# FiltroRF.net
KiCad netlist of a schematic drawn in Altium Designer
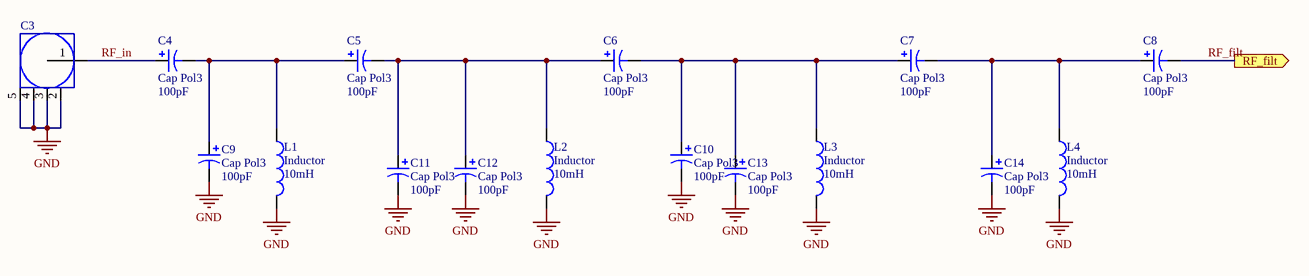
[diagram p0: FiltroRF.SchDoc]

(export (version "E")
  (design (tool "Eeschema 10.0.6"))
  (components
    (comp (ref "C3") (value "SMA") (footprint "SMA1") (libsource (lib "epf") (part "SMA")))
    (comp (ref "C4")
      (value "Cap Pol3")
      (footprint "C0805")
      (description "Polarized Capacitor (Surface Mount)")
      (fields (field (name "ALTIUM_VALUE") "100pF") (field (name "PUBLISHER") "Altium Limited"))
      (libsource (lib "Miscellaneous Devices") (part "Cap Pol3"))
    )
    (comp (ref "C5")
      (value "Cap Pol3")
      (footprint "C0805")
      (description "Polarized Capacitor (Surface Mount)")
      (fields (field (name "ALTIUM_VALUE") "100pF") (field (name "PUBLISHER") "Altium Limited"))
      (libsource (lib "Miscellaneous Devices") (part "Cap Pol3"))
    )
    (comp (ref "C6")
      (value "Cap Pol3")
      (footprint "C0805")
      (description "Polarized Capacitor (Surface Mount)")
      (fields (field (name "ALTIUM_VALUE") "100pF") (field (name "PUBLISHER") "Altium Limited"))
      (libsource (lib "Miscellaneous Devices") (part "Cap Pol3"))
    )
    (comp (ref "C7")
      (value "Cap Pol3")
      (footprint "C0805")
      (description "Polarized Capacitor (Surface Mount)")
      (fields (field (name "ALTIUM_VALUE") "100pF") (field (name "PUBLISHER") "Altium Limited"))
      (libsource (lib "Miscellaneous Devices") (part "Cap Pol3"))
    )
    (comp (ref "C8")
      (value "Cap Pol3")
      (footprint "C0805")
      (description "Polarized Capacitor (Surface Mount)")
      (fields (field (name "ALTIUM_VALUE") "100pF") (field (name "PUBLISHER") "Altium Limited"))
      (libsource (lib "Miscellaneous Devices") (part "Cap Pol3"))
    )
    (comp (ref "C9")
      (value "Cap Pol3")
      (footprint "C0805")
      (description "Polarized Capacitor (Surface Mount)")
      (fields (field (name "ALTIUM_VALUE") "100pF") (field (name "PUBLISHER") "Altium Limited"))
      (libsource (lib "Miscellaneous Devices") (part "Cap Pol3"))
    )
    (comp (ref "C10")
      (value "Cap Pol3")
      (footprint "C0805")
      (description "Polarized Capacitor (Surface Mount)")
      (fields (field (name "ALTIUM_VALUE") "100pF") (field (name "PUBLISHER") "Altium Limited"))
      (libsource (lib "Miscellaneous Devices") (part "Cap Pol3"))
    )
    (comp (ref "C11")
      (value "Cap Pol3")
      (footprint "C0805")
      (description "Polarized Capacitor (Surface Mount)")
      (fields (field (name "ALTIUM_VALUE") "100pF") (field (name "PUBLISHER") "Altium Limited"))
      (libsource (lib "Miscellaneous Devices") (part "Cap Pol3"))
    )
    (comp (ref "C12")
      (value "Cap Pol3")
      (footprint "C0805")
      (description "Polarized Capacitor (Surface Mount)")
      (fields (field (name "ALTIUM_VALUE") "100pF") (field (name "PUBLISHER") "Altium Limited"))
      (libsource (lib "Miscellaneous Devices") (part "Cap Pol3"))
    )
    (comp (ref "C13")
      (value "Cap Pol3")
      (footprint "C0805")
      (description "Polarized Capacitor (Surface Mount)")
      (fields (field (name "ALTIUM_VALUE") "100pF") (field (name "PUBLISHER") "Altium Limited"))
      (libsource (lib "Miscellaneous Devices") (part "Cap Pol3"))
    )
    (comp (ref "C14")
      (value "Cap Pol3")
      (footprint "C0805")
      (description "Polarized Capacitor (Surface Mount)")
      (fields (field (name "ALTIUM_VALUE") "100pF") (field (name "PUBLISHER") "Altium Limited"))
      (libsource (lib "Miscellaneous Devices") (part "Cap Pol3"))
    )
    (comp (ref "L1")
      (value "Inductor")
      (footprint "3261")
      (fields (field (name "ALTIUM_VALUE") "10mH") (field (name "PUBLISHER") "Altium Limited"))
      (libsource (lib "Miscellaneous Devices") (part "Inductor"))
    )
    (comp (ref "L2")
      (value "Inductor")
      (footprint "3261")
      (fields (field (name "ALTIUM_VALUE") "10mH") (field (name "PUBLISHER") "Altium Limited"))
      (libsource (lib "Miscellaneous Devices") (part "Inductor"))
    )
    (comp (ref "L3")
      (value "Inductor")
      (footprint "3261")
      (fields (field (name "ALTIUM_VALUE") "10mH") (field (name "PUBLISHER") "Altium Limited"))
      (libsource (lib "Miscellaneous Devices") (part "Inductor"))
    )
    (comp (ref "L4")
      (value "Inductor")
      (footprint "3261")
      (fields (field (name "ALTIUM_VALUE") "10mH") (field (name "PUBLISHER") "Altium Limited"))
      (libsource (lib "Miscellaneous Devices") (part "Inductor"))
    )
  )
  (nets
    (net (code "1") (name "/RF_filt") (class "Default")
      (node (ref "C8") (pin "2") (pinfunction "2_2") (pintype "passive"))
    )
    (net (code "2") (name "/RF_in") (class "Default")
      (node (ref "C3") (pin "1") (pinfunction "RF_1") (pintype "passive"))
      (node (ref "C4") (pin "1") (pinfunction "1_1") (pintype "passive"))
    )
    (net (code "3") (name "GND") (class "Default")
      (node (ref "C10") (pin "2") (pinfunction "2_2") (pintype "passive"))
      (node (ref "C11") (pin "2") (pinfunction "2_2") (pintype "passive"))
      (node (ref "C12") (pin "2") (pinfunction "2_2") (pintype "passive"))
      (node (ref "C13") (pin "2") (pinfunction "2_2") (pintype "passive"))
      (node (ref "C14") (pin "2") (pinfunction "2_2") (pintype "passive"))
      (node (ref "C3") (pin "2") (pinfunction "GND_2") (pintype "passive"))
      (node (ref "C3") (pin "3") (pinfunction "GND_3") (pintype "passive"))
      (node (ref "C3") (pin "4") (pinfunction "GND_4") (pintype "passive"))
      (node (ref "C3") (pin "5") (pinfunction "GND_5") (pintype "passive"))
      (node (ref "C9") (pin "2") (pinfunction "2_2") (pintype "passive"))
      (node (ref "L1") (pin "2") (pinfunction "2_2") (pintype "passive"))
      (node (ref "L2") (pin "2") (pinfunction "2_2") (pintype "passive"))
      (node (ref "L3") (pin "2") (pinfunction "2_2") (pintype "passive"))
      (node (ref "L4") (pin "2") (pinfunction "2_2") (pintype "passive"))
    )
    (net (code "4") (name "Net-(C4-Pad2)") (class "Default")
      (node (ref "C4") (pin "2") (pinfunction "2_2") (pintype "passive"))
      (node (ref "C5") (pin "1") (pinfunction "1_1") (pintype "passive"))
      (node (ref "C9") (pin "1") (pinfunction "1_1") (pintype "passive"))
      (node (ref "L1") (pin "1") (pinfunction "1_1") (pintype "passive"))
    )
    (net (code "5") (name "Net-(C10-Pad1)") (class "Default")
      (node (ref "C10") (pin "1") (pinfunction "1_1") (pintype "passive"))
      (node (ref "C13") (pin "1") (pinfunction "1_1") (pintype "passive"))
      (node (ref "C6") (pin "2") (pinfunction "2_2") (pintype "passive"))
      (node (ref "C7") (pin "1") (pinfunction "1_1") (pintype "passive"))
      (node (ref "L3") (pin "1") (pinfunction "1_1") (pintype "passive"))
    )
    (net (code "6") (name "Net-(C11-Pad1)") (class "Default")
      (node (ref "C11") (pin "1") (pinfunction "1_1") (pintype "passive"))
      (node (ref "C12") (pin "1") (pinfunction "1_1") (pintype "passive"))
      (node (ref "C5") (pin "2") (pinfunction "2_2") (pintype "passive"))
      (node (ref "C6") (pin "1") (pinfunction "1_1") (pintype "passive"))
      (node (ref "L2") (pin "1") (pinfunction "1_1") (pintype "passive"))
    )
    (net (code "7") (name "Net-(C14-Pad1)") (class "Default")
      (node (ref "C14") (pin "1") (pinfunction "1_1") (pintype "passive"))
      (node (ref "C7") (pin "2") (pinfunction "2_2") (pintype "passive"))
      (node (ref "C8") (pin "1") (pinfunction "1_1") (pintype "passive"))
      (node (ref "L4") (pin "1") (pinfunction "1_1") (pintype "passive"))
    )
  )
)
